# LDO_3v3_LM2937.net
KiCad netlist of a schematic drawn in Altium Designer
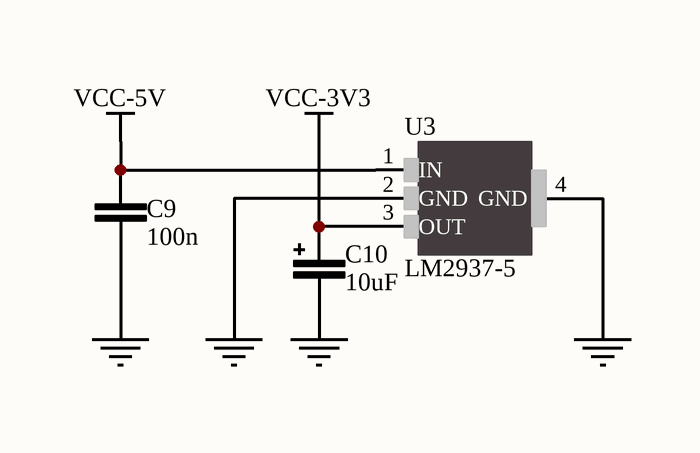
[diagram p0: LDO_3v3_LM2937.SchDoc]

(export (version "E")
  (design (tool "Eeschema 10.0.6"))
  (components
    (comp (ref "C9")
      (value "100n")
      (footprint "CER_0603")
      (description "CAP CER 100n 10V X5R 10% 0603")
      (libsource (lib "Capacitors") (part "06032105"))
    )
    (comp (ref "C10")
      (value "10uF")
      (footprint "TANT_1210")
      (description "CAP TANT 10u")
      (libsource (lib "Capacitors") (part "00001106"))
    )
    (comp (ref "U3")
      (value "LM2937-5")
      (footprint "Integrated_circuits:SOT223")
      (description "IC REG LINEAR 5V 400MA SOT223-4")
      (libsource (lib "Integrated_circuits") (part "00000007"))
    )
  )
  (nets
    (net (code "1") (name "GND") (class "Default")
      (node (ref "C10") (pin "2") (pinfunction "2_2") (pintype "passive"))
      (node (ref "C9") (pin "1") (pinfunction "1_1") (pintype "passive"))
      (node (ref "U3") (pin "2") (pinfunction "GND_2") (pintype "passive"))
      (node (ref "U3") (pin "4") (pinfunction "GND_4") (pintype "passive"))
    )
    (net (code "2") (name "VCC-3V3") (class "Default")
      (node (ref "C10") (pin "1") (pinfunction "1_1") (pintype "passive"))
      (node (ref "U3") (pin "3") (pinfunction "OUT_3") (pintype "passive"))
    )
    (net (code "3") (name "VCC-5V") (class "Default")
      (node (ref "C9") (pin "2") (pinfunction "2_2") (pintype "passive"))
      (node (ref "U3") (pin "1") (pinfunction "IN_1") (pintype "passive"))
    )
  )
)
